# fetmatcher.net
KiCad netlist of a schematic drawn in EAGLE
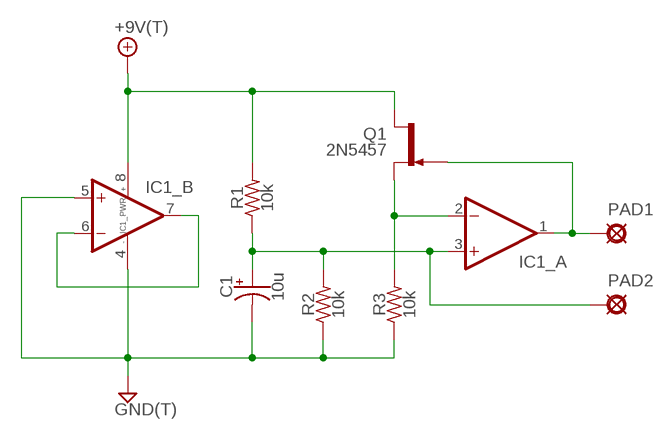
[diagram p0: schematic, sheet 1]

(export (version "E")
  (design (tool "Eeschema 10.0.6"))
  (components
    (comp (ref "+9V1")
      (value "+9V(T)")
      (footprint "eagle-import:SQUARE")
      (libsource (lib "eagle-import") (part "+9V(T)"))
    )
    (comp (ref "C1")
      (value "10u")
      (footprint "eagle-import:050_020_1")
      (libsource (lib "eagle-import") (part "0501"))
    )
    (comp (ref "GND1")
      (value "GND(T)")
      (footprint "eagle-import:SQUARE")
      (libsource (lib "eagle-import") (part "GND(T)"))
    )
    (comp (ref "IC1")
      (value "DUALTH")
      (footprint "eagle-import:DIL0")
      (libsource (lib "eagle-import") (part "DUALTH"))
    )
    (comp (ref "PAD1")
      (value "PAD")
      (footprint "eagle-import:SQUARE")
      (libsource (lib "eagle-import") (part "PAD"))
    )
    (comp (ref "PAD2")
      (value "PAD")
      (footprint "eagle-import:SQUARE")
      (libsource (lib "eagle-import") (part "PAD"))
    )
    (comp (ref "Q1")
      (value "2N5457")
      (footprint "eagle-import:TO92-")
      (libsource (lib "eagle-import") (part "2N5457"))
    )
    (comp (ref "R1")
      (value "10k")
      (footprint "eagle-import:R0207_3")
      (libsource (lib "eagle-import") (part "R_.3B"))
    )
    (comp (ref "R2")
      (value "10k")
      (footprint "eagle-import:R0207_3")
      (libsource (lib "eagle-import") (part "R_.3B"))
    )
    (comp (ref "R3")
      (value "10k")
      (footprint "eagle-import:R0207_3")
      (libsource (lib "eagle-import") (part "R_.3B"))
    )
  )
  (nets
    (net (code "1") (name "+9V(T)") (class "Default")
      (node (ref "+9V1") (pin "1") (pinfunction "+9V_1") (pintype "power_in"))
      (node (ref "IC1") (pin "8") (pinfunction "V+_8") (pintype "power_in"))
      (node (ref "Q1") (pin "3") (pinfunction "D_3") (pintype "passive"))
      (node (ref "R1") (pin "2") (pinfunction "2_2") (pintype "passive"))
    )
    (net (code "2") (name "GND(T)") (class "Default")
      (node (ref "C1") (pin "-") (pinfunction "-_-") (pintype "passive"))
      (node (ref "GND1") (pin "1") (pinfunction "GND_1") (pintype "power_in"))
      (node (ref "IC1") (pin "4") (pinfunction "V-_4") (pintype "power_in"))
      (node (ref "IC1") (pin "5") (pinfunction "+IN_5") (pintype "input"))
      (node (ref "R2") (pin "1") (pinfunction "1_1") (pintype "passive"))
      (node (ref "R3") (pin "1") (pinfunction "1_1") (pintype "passive"))
    )
    (net (code "3") (name "Net-(IC1A-+IN)") (class "Default")
      (node (ref "C1") (pin "+") (pinfunction "+_+") (pintype "passive"))
      (node (ref "IC1") (pin "3") (pinfunction "+IN_3") (pintype "input"))
      (node (ref "PAD2") (pin "1") (pinfunction "PAD_1") (pintype "passive"))
      (node (ref "R1") (pin "1") (pinfunction "1_1") (pintype "passive"))
      (node (ref "R2") (pin "2") (pinfunction "2_2") (pintype "passive"))
    )
    (net (code "4") (name "Net-(IC1A--IN)") (class "Default")
      (node (ref "IC1") (pin "2") (pinfunction "-IN_2") (pintype "input"))
      (node (ref "Q1") (pin "2") (pinfunction "S_2") (pintype "passive"))
      (node (ref "R3") (pin "2") (pinfunction "2_2") (pintype "passive"))
    )
    (net (code "5") (name "Net-(IC1A-OUT)") (class "Default")
      (node (ref "IC1") (pin "1") (pinfunction "OUT_1") (pintype "output"))
      (node (ref "PAD1") (pin "1") (pinfunction "PAD_1") (pintype "passive"))
      (node (ref "Q1") (pin "1") (pinfunction "G_1") (pintype "passive"))
    )
    (net (code "6") (name "Net-(IC1B--IN)") (class "Default")
      (node (ref "IC1") (pin "6") (pinfunction "-IN_6") (pintype "input"))
      (node (ref "IC1") (pin "7") (pinfunction "OUT_7") (pintype "output"))
    )
  )
)
